# Output_For_Relay.net
KiCad netlist of a schematic drawn in Altium Designer
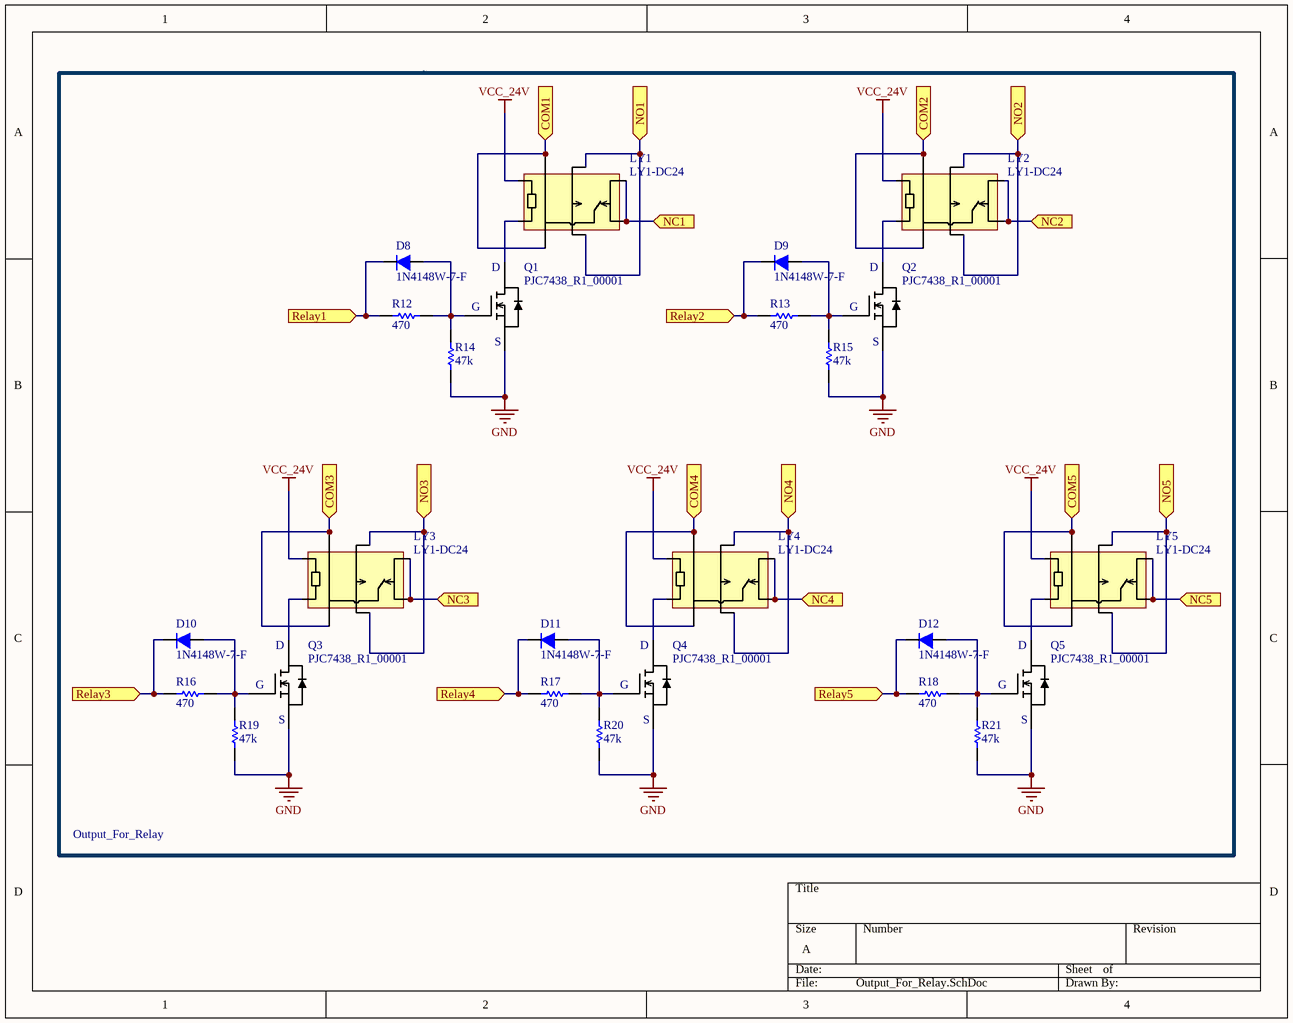
[diagram p0: Output_For_Relay.SchDoc]

(export (version "E")
  (design (tool "Eeschema 10.0.6"))
  (components
    (comp (ref "D8")
      (value "1N4148W-7-F")
      (footprint "1N4148")
      (description "Diode Standard 100 V 300mA (DC) Surface Mount SOD-123")
      (fields (field (name "MFR") "Diodes Incorporated"))
      (libsource (lib "Integrated_Library1") (part "1N4148"))
    )
    (comp (ref "D9")
      (value "1N4148W-7-F")
      (footprint "1N4148")
      (description "Diode Standard 100 V 300mA (DC) Surface Mount SOD-123")
      (fields (field (name "MFR") "Diodes Incorporated"))
      (libsource (lib "Integrated_Library1") (part "1N4148"))
    )
    (comp (ref "D10")
      (value "1N4148W-7-F")
      (footprint "1N4148")
      (description "Diode Standard 100 V 300mA (DC) Surface Mount SOD-123")
      (fields (field (name "MFR") "Diodes Incorporated"))
      (libsource (lib "Integrated_Library1") (part "1N4148"))
    )
    (comp (ref "D11")
      (value "1N4148W-7-F")
      (footprint "1N4148")
      (description "Diode Standard 100 V 300mA (DC) Surface Mount SOD-123")
      (fields (field (name "MFR") "Diodes Incorporated"))
      (libsource (lib "Integrated_Library1") (part "1N4148"))
    )
    (comp (ref "D12")
      (value "1N4148W-7-F")
      (footprint "1N4148")
      (description "Diode Standard 100 V 300mA (DC) Surface Mount SOD-123")
      (fields (field (name "MFR") "Diodes Incorporated"))
      (libsource (lib "Integrated_Library1") (part "1N4148"))
    )
    (comp (ref "LY1")
      (value "LY1-DC24")
      (footprint "LY1-DC24")
      (description "General Purpose Relay SPDT (1 Form C) 24VDC Coil Socketable")
      (fields (field (name "MFR") "Omron Automation and Safety"))
      (libsource (lib "YenDoo") (part "LY1-DC24"))
    )
    (comp (ref "LY2")
      (value "LY1-DC24")
      (footprint "LY1-DC24")
      (description "General Purpose Relay SPDT (1 Form C) 24VDC Coil Socketable")
      (fields (field (name "MFR") "Omron Automation and Safety"))
      (libsource (lib "YenDoo") (part "LY1-DC24"))
    )
    (comp (ref "LY3")
      (value "LY1-DC24")
      (footprint "LY1-DC24")
      (description "General Purpose Relay SPDT (1 Form C) 24VDC Coil Socketable")
      (fields (field (name "MFR") "Omron Automation and Safety"))
      (libsource (lib "YenDoo") (part "LY1-DC24"))
    )
    (comp (ref "LY4")
      (value "LY1-DC24")
      (footprint "LY1-DC24")
      (description "General Purpose Relay SPDT (1 Form C) 24VDC Coil Socketable")
      (fields (field (name "MFR") "Omron Automation and Safety"))
      (libsource (lib "YenDoo") (part "LY1-DC24"))
    )
    (comp (ref "LY5")
      (value "LY1-DC24")
      (footprint "LY1-DC24")
      (description "General Purpose Relay SPDT (1 Form C) 24VDC Coil Socketable")
      (fields (field (name "MFR") "Omron Automation and Safety"))
      (libsource (lib "YenDoo") (part "LY1-DC24"))
    )
    (comp (ref "Q1")
      (value "PJC7438_R1_00001")
      (footprint "PJC7438")
      (description "N-Channel 50 V 400mA (Ta) 350mW (Ta) Surface Mount SOT-323")
      (fields (field (name "MFR") "Panjit International Inc."))
      (libsource (lib "Integrated_Library1") (part "PJC7438"))
    )
    (comp (ref "Q2")
      (value "PJC7438_R1_00001")
      (footprint "PJC7438")
      (description "N-Channel 50 V 400mA (Ta) 350mW (Ta) Surface Mount SOT-323")
      (fields (field (name "MFR") "Panjit International Inc."))
      (libsource (lib "Integrated_Library1") (part "PJC7438"))
    )
    (comp (ref "Q3")
      (value "PJC7438_R1_00001")
      (footprint "PJC7438")
      (description "N-Channel 50 V 400mA (Ta) 350mW (Ta) Surface Mount SOT-323")
      (fields (field (name "MFR") "Panjit International Inc."))
      (libsource (lib "Integrated_Library1") (part "PJC7438"))
    )
    (comp (ref "Q4")
      (value "PJC7438_R1_00001")
      (footprint "PJC7438")
      (description "N-Channel 50 V 400mA (Ta) 350mW (Ta) Surface Mount SOT-323")
      (fields (field (name "MFR") "Panjit International Inc."))
      (libsource (lib "Integrated_Library1") (part "PJC7438"))
    )
    (comp (ref "Q5")
      (value "PJC7438_R1_00001")
      (footprint "PJC7438")
      (description "N-Channel 50 V 400mA (Ta) 350mW (Ta) Surface Mount SOT-323")
      (fields (field (name "MFR") "Panjit International Inc."))
      (libsource (lib "Integrated_Library1") (part "PJC7438"))
    )
    (comp (ref "R12")
      (value "470")
      (footprint "RES-SM-0603")
      (description "RES SMD 470 OHM 5% 1/4W 0603")
      (fields (field (name "MFR") "Rohm Semiconductor") (field (name "TOLERANCE") "±5%"))
      (libsource (lib "PIF_Library") (part "RESISTOR SMD"))
    )
    (comp (ref "R13")
      (value "470")
      (footprint "RES-SM-0603")
      (description "RES SMD 470 OHM 5% 1/4W 0603")
      (fields (field (name "MFR") "Rohm Semiconductor") (field (name "TOLERANCE") "±5%"))
      (libsource (lib "PIF_Library") (part "RESISTOR SMD"))
    )
    (comp (ref "R14")
      (value "47k")
      (footprint "RES-SM-0603")
      (description "RES SMD 47K OHM 5% 1/4W 0603")
      (fields (field (name "MFR") "Rohm Semiconductor") (field (name "TOLERANCE") "±5%"))
      (libsource (lib "PIF_Library") (part "RESISTOR SMD"))
    )
    (comp (ref "R15")
      (value "47k")
      (footprint "RES-SM-0603")
      (description "RES SMD 47K OHM 5% 1/4W 0603")
      (fields (field (name "MFR") "Rohm Semiconductor") (field (name "TOLERANCE") "±5%"))
      (libsource (lib "PIF_Library") (part "RESISTOR SMD"))
    )
    (comp (ref "R16")
      (value "470")
      (footprint "RES-SM-0603")
      (description "RES SMD 470 OHM 5% 1/4W 0603")
      (fields (field (name "MFR") "Rohm Semiconductor") (field (name "TOLERANCE") "±5%"))
      (libsource (lib "PIF_Library") (part "RESISTOR SMD"))
    )
    (comp (ref "R17")
      (value "470")
      (footprint "RES-SM-0603")
      (description "RES SMD 470 OHM 5% 1/4W 0603")
      (fields (field (name "MFR") "Rohm Semiconductor") (field (name "TOLERANCE") "±5%"))
      (libsource (lib "PIF_Library") (part "RESISTOR SMD"))
    )
    (comp (ref "R18")
      (value "470")
      (footprint "RES-SM-0603")
      (description "RES SMD 470 OHM 5% 1/4W 0603")
      (fields (field (name "MFR") "Rohm Semiconductor") (field (name "TOLERANCE") "±5%"))
      (libsource (lib "PIF_Library") (part "RESISTOR SMD"))
    )
    (comp (ref "R19")
      (value "47k")
      (footprint "RES-SM-0603")
      (description "RES SMD 47K OHM 5% 1/4W 0603")
      (fields (field (name "MFR") "Rohm Semiconductor") (field (name "TOLERANCE") "±5%"))
      (libsource (lib "PIF_Library") (part "RESISTOR SMD"))
    )
    (comp (ref "R20")
      (value "47k")
      (footprint "RES-SM-0603")
      (description "RES SMD 47K OHM 5% 1/4W 0603")
      (fields (field (name "MFR") "Rohm Semiconductor") (field (name "TOLERANCE") "±5%"))
      (libsource (lib "PIF_Library") (part "RESISTOR SMD"))
    )
    (comp (ref "R21")
      (value "47k")
      (footprint "RES-SM-0603")
      (description "RES SMD 47K OHM 5% 1/4W 0603")
      (fields (field (name "MFR") "Rohm Semiconductor") (field (name "TOLERANCE") "±5%"))
      (libsource (lib "PIF_Library") (part "RESISTOR SMD"))
    )
  )
  (nets
    (net (code "1") (name "/COM1") (class "Default")
      (node (ref "LY1") (pin "5") (pinfunction "5_5") (pintype "passive"))
      (node (ref "LY1") (pin "6") (pinfunction "6_6") (pintype "passive"))
    )
    (net (code "2") (name "/COM2") (class "Default")
      (node (ref "LY2") (pin "5") (pinfunction "5_5") (pintype "passive"))
      (node (ref "LY2") (pin "6") (pinfunction "6_6") (pintype "passive"))
    )
    (net (code "3") (name "/COM3") (class "Default")
      (node (ref "LY3") (pin "5") (pinfunction "5_5") (pintype "passive"))
      (node (ref "LY3") (pin "6") (pinfunction "6_6") (pintype "passive"))
    )
    (net (code "4") (name "/COM4") (class "Default")
      (node (ref "LY4") (pin "5") (pinfunction "5_5") (pintype "passive"))
      (node (ref "LY4") (pin "6") (pinfunction "6_6") (pintype "passive"))
    )
    (net (code "5") (name "/COM5") (class "Default")
      (node (ref "LY5") (pin "5") (pinfunction "5_5") (pintype "passive"))
      (node (ref "LY5") (pin "6") (pinfunction "6_6") (pintype "passive"))
    )
    (net (code "6") (name "/NC1") (class "Default")
      (node (ref "LY1") (pin "1") (pinfunction "1_1") (pintype "passive"))
      (node (ref "LY1") (pin "2") (pinfunction "2_2") (pintype "passive"))
    )
    (net (code "7") (name "/NC2") (class "Default")
      (node (ref "LY2") (pin "1") (pinfunction "1_1") (pintype "passive"))
      (node (ref "LY2") (pin "2") (pinfunction "2_2") (pintype "passive"))
    )
    (net (code "8") (name "/NC3") (class "Default")
      (node (ref "LY3") (pin "1") (pinfunction "1_1") (pintype "passive"))
      (node (ref "LY3") (pin "2") (pinfunction "2_2") (pintype "passive"))
    )
    (net (code "9") (name "/NC4") (class "Default")
      (node (ref "LY4") (pin "1") (pinfunction "1_1") (pintype "passive"))
      (node (ref "LY4") (pin "2") (pinfunction "2_2") (pintype "passive"))
    )
    (net (code "10") (name "/NC5") (class "Default")
      (node (ref "LY5") (pin "1") (pinfunction "1_1") (pintype "passive"))
      (node (ref "LY5") (pin "2") (pinfunction "2_2") (pintype "passive"))
    )
    (net (code "11") (name "/NO1") (class "Default")
      (node (ref "LY1") (pin "3") (pinfunction "3_3") (pintype "passive"))
      (node (ref "LY1") (pin "4") (pinfunction "4_4") (pintype "passive"))
    )
    (net (code "12") (name "/NO2") (class "Default")
      (node (ref "LY2") (pin "3") (pinfunction "3_3") (pintype "passive"))
      (node (ref "LY2") (pin "4") (pinfunction "4_4") (pintype "passive"))
    )
    (net (code "13") (name "/NO3") (class "Default")
      (node (ref "LY3") (pin "3") (pinfunction "3_3") (pintype "passive"))
      (node (ref "LY3") (pin "4") (pinfunction "4_4") (pintype "passive"))
    )
    (net (code "14") (name "/NO4") (class "Default")
      (node (ref "LY4") (pin "3") (pinfunction "3_3") (pintype "passive"))
      (node (ref "LY4") (pin "4") (pinfunction "4_4") (pintype "passive"))
    )
    (net (code "15") (name "/NO5") (class "Default")
      (node (ref "LY5") (pin "3") (pinfunction "3_3") (pintype "passive"))
      (node (ref "LY5") (pin "4") (pinfunction "4_4") (pintype "passive"))
    )
    (net (code "16") (name "/Relay1") (class "Default")
      (node (ref "D8") (pin "2") (pinfunction "K_2") (pintype "passive"))
      (node (ref "R12") (pin "2") (pinfunction "2_2") (pintype "passive"))
    )
    (net (code "17") (name "/Relay2") (class "Default")
      (node (ref "D9") (pin "2") (pinfunction "K_2") (pintype "passive"))
      (node (ref "R13") (pin "2") (pinfunction "2_2") (pintype "passive"))
    )
    (net (code "18") (name "/Relay3") (class "Default")
      (node (ref "D10") (pin "2") (pinfunction "K_2") (pintype "passive"))
      (node (ref "R16") (pin "2") (pinfunction "2_2") (pintype "passive"))
    )
    (net (code "19") (name "/Relay4") (class "Default")
      (node (ref "D11") (pin "2") (pinfunction "K_2") (pintype "passive"))
      (node (ref "R17") (pin "2") (pinfunction "2_2") (pintype "passive"))
    )
    (net (code "20") (name "/Relay5") (class "Default")
      (node (ref "D12") (pin "2") (pinfunction "K_2") (pintype "passive"))
      (node (ref "R18") (pin "2") (pinfunction "2_2") (pintype "passive"))
    )
    (net (code "21") (name "GND") (class "Default")
      (node (ref "Q1") (pin "2") (pinfunction "S_2") (pintype "passive"))
      (node (ref "Q2") (pin "2") (pinfunction "S_2") (pintype "passive"))
      (node (ref "Q3") (pin "2") (pinfunction "S_2") (pintype "passive"))
      (node (ref "Q4") (pin "2") (pinfunction "S_2") (pintype "passive"))
      (node (ref "Q5") (pin "2") (pinfunction "S_2") (pintype "passive"))
      (node (ref "R14") (pin "2") (pinfunction "2_2") (pintype "passive"))
      (node (ref "R15") (pin "2") (pinfunction "2_2") (pintype "passive"))
      (node (ref "R19") (pin "2") (pinfunction "2_2") (pintype "passive"))
      (node (ref "R20") (pin "2") (pinfunction "2_2") (pintype "passive"))
      (node (ref "R21") (pin "2") (pinfunction "2_2") (pintype "passive"))
    )
    (net (code "22") (name "Net-(D8-A)") (class "Default")
      (node (ref "D8") (pin "1") (pinfunction "A_1") (pintype "passive"))
      (node (ref "Q1") (pin "1") (pinfunction "G_1") (pintype "passive"))
      (node (ref "R12") (pin "1") (pinfunction "1_1") (pintype "passive"))
      (node (ref "R14") (pin "1") (pinfunction "1_1") (pintype "passive"))
    )
    (net (code "23") (name "Net-(D9-A)") (class "Default")
      (node (ref "D9") (pin "1") (pinfunction "A_1") (pintype "passive"))
      (node (ref "Q2") (pin "1") (pinfunction "G_1") (pintype "passive"))
      (node (ref "R13") (pin "1") (pinfunction "1_1") (pintype "passive"))
      (node (ref "R15") (pin "1") (pinfunction "1_1") (pintype "passive"))
    )
    (net (code "24") (name "Net-(D10-A)") (class "Default")
      (node (ref "D10") (pin "1") (pinfunction "A_1") (pintype "passive"))
      (node (ref "Q3") (pin "1") (pinfunction "G_1") (pintype "passive"))
      (node (ref "R16") (pin "1") (pinfunction "1_1") (pintype "passive"))
      (node (ref "R19") (pin "1") (pinfunction "1_1") (pintype "passive"))
    )
    (net (code "25") (name "Net-(D11-A)") (class "Default")
      (node (ref "D11") (pin "1") (pinfunction "A_1") (pintype "passive"))
      (node (ref "Q4") (pin "1") (pinfunction "G_1") (pintype "passive"))
      (node (ref "R17") (pin "1") (pinfunction "1_1") (pintype "passive"))
      (node (ref "R20") (pin "1") (pinfunction "1_1") (pintype "passive"))
    )
    (net (code "26") (name "Net-(D12-A)") (class "Default")
      (node (ref "D12") (pin "1") (pinfunction "A_1") (pintype "passive"))
      (node (ref "Q5") (pin "1") (pinfunction "G_1") (pintype "passive"))
      (node (ref "R18") (pin "1") (pinfunction "1_1") (pintype "passive"))
      (node (ref "R21") (pin "1") (pinfunction "1_1") (pintype "passive"))
    )
    (net (code "27") (name "Net-(Q1-D)") (class "Default")
      (node (ref "LY1") (pin "8") (pinfunction "8_8") (pintype "passive"))
      (node (ref "Q1") (pin "3") (pinfunction "D_3") (pintype "passive"))
    )
    (net (code "28") (name "Net-(Q2-D)") (class "Default")
      (node (ref "LY2") (pin "8") (pinfunction "8_8") (pintype "passive"))
      (node (ref "Q2") (pin "3") (pinfunction "D_3") (pintype "passive"))
    )
    (net (code "29") (name "Net-(Q3-D)") (class "Default")
      (node (ref "LY3") (pin "8") (pinfunction "8_8") (pintype "passive"))
      (node (ref "Q3") (pin "3") (pinfunction "D_3") (pintype "passive"))
    )
    (net (code "30") (name "Net-(Q4-D)") (class "Default")
      (node (ref "LY4") (pin "8") (pinfunction "8_8") (pintype "passive"))
      (node (ref "Q4") (pin "3") (pinfunction "D_3") (pintype "passive"))
    )
    (net (code "31") (name "Net-(Q5-D)") (class "Default")
      (node (ref "LY5") (pin "8") (pinfunction "8_8") (pintype "passive"))
      (node (ref "Q5") (pin "3") (pinfunction "D_3") (pintype "passive"))
    )
    (net (code "32") (name "VCC_24V") (class "Default")
      (node (ref "LY1") (pin "7") (pinfunction "7_7") (pintype "passive"))
      (node (ref "LY2") (pin "7") (pinfunction "7_7") (pintype "passive"))
      (node (ref "LY3") (pin "7") (pinfunction "7_7") (pintype "passive"))
      (node (ref "LY4") (pin "7") (pinfunction "7_7") (pintype "passive"))
      (node (ref "LY5") (pin "7") (pinfunction "7_7") (pintype "passive"))
    )
  )
)
